# CYUSB_IO.net
KiCad netlist of a schematic drawn in Altium Designer
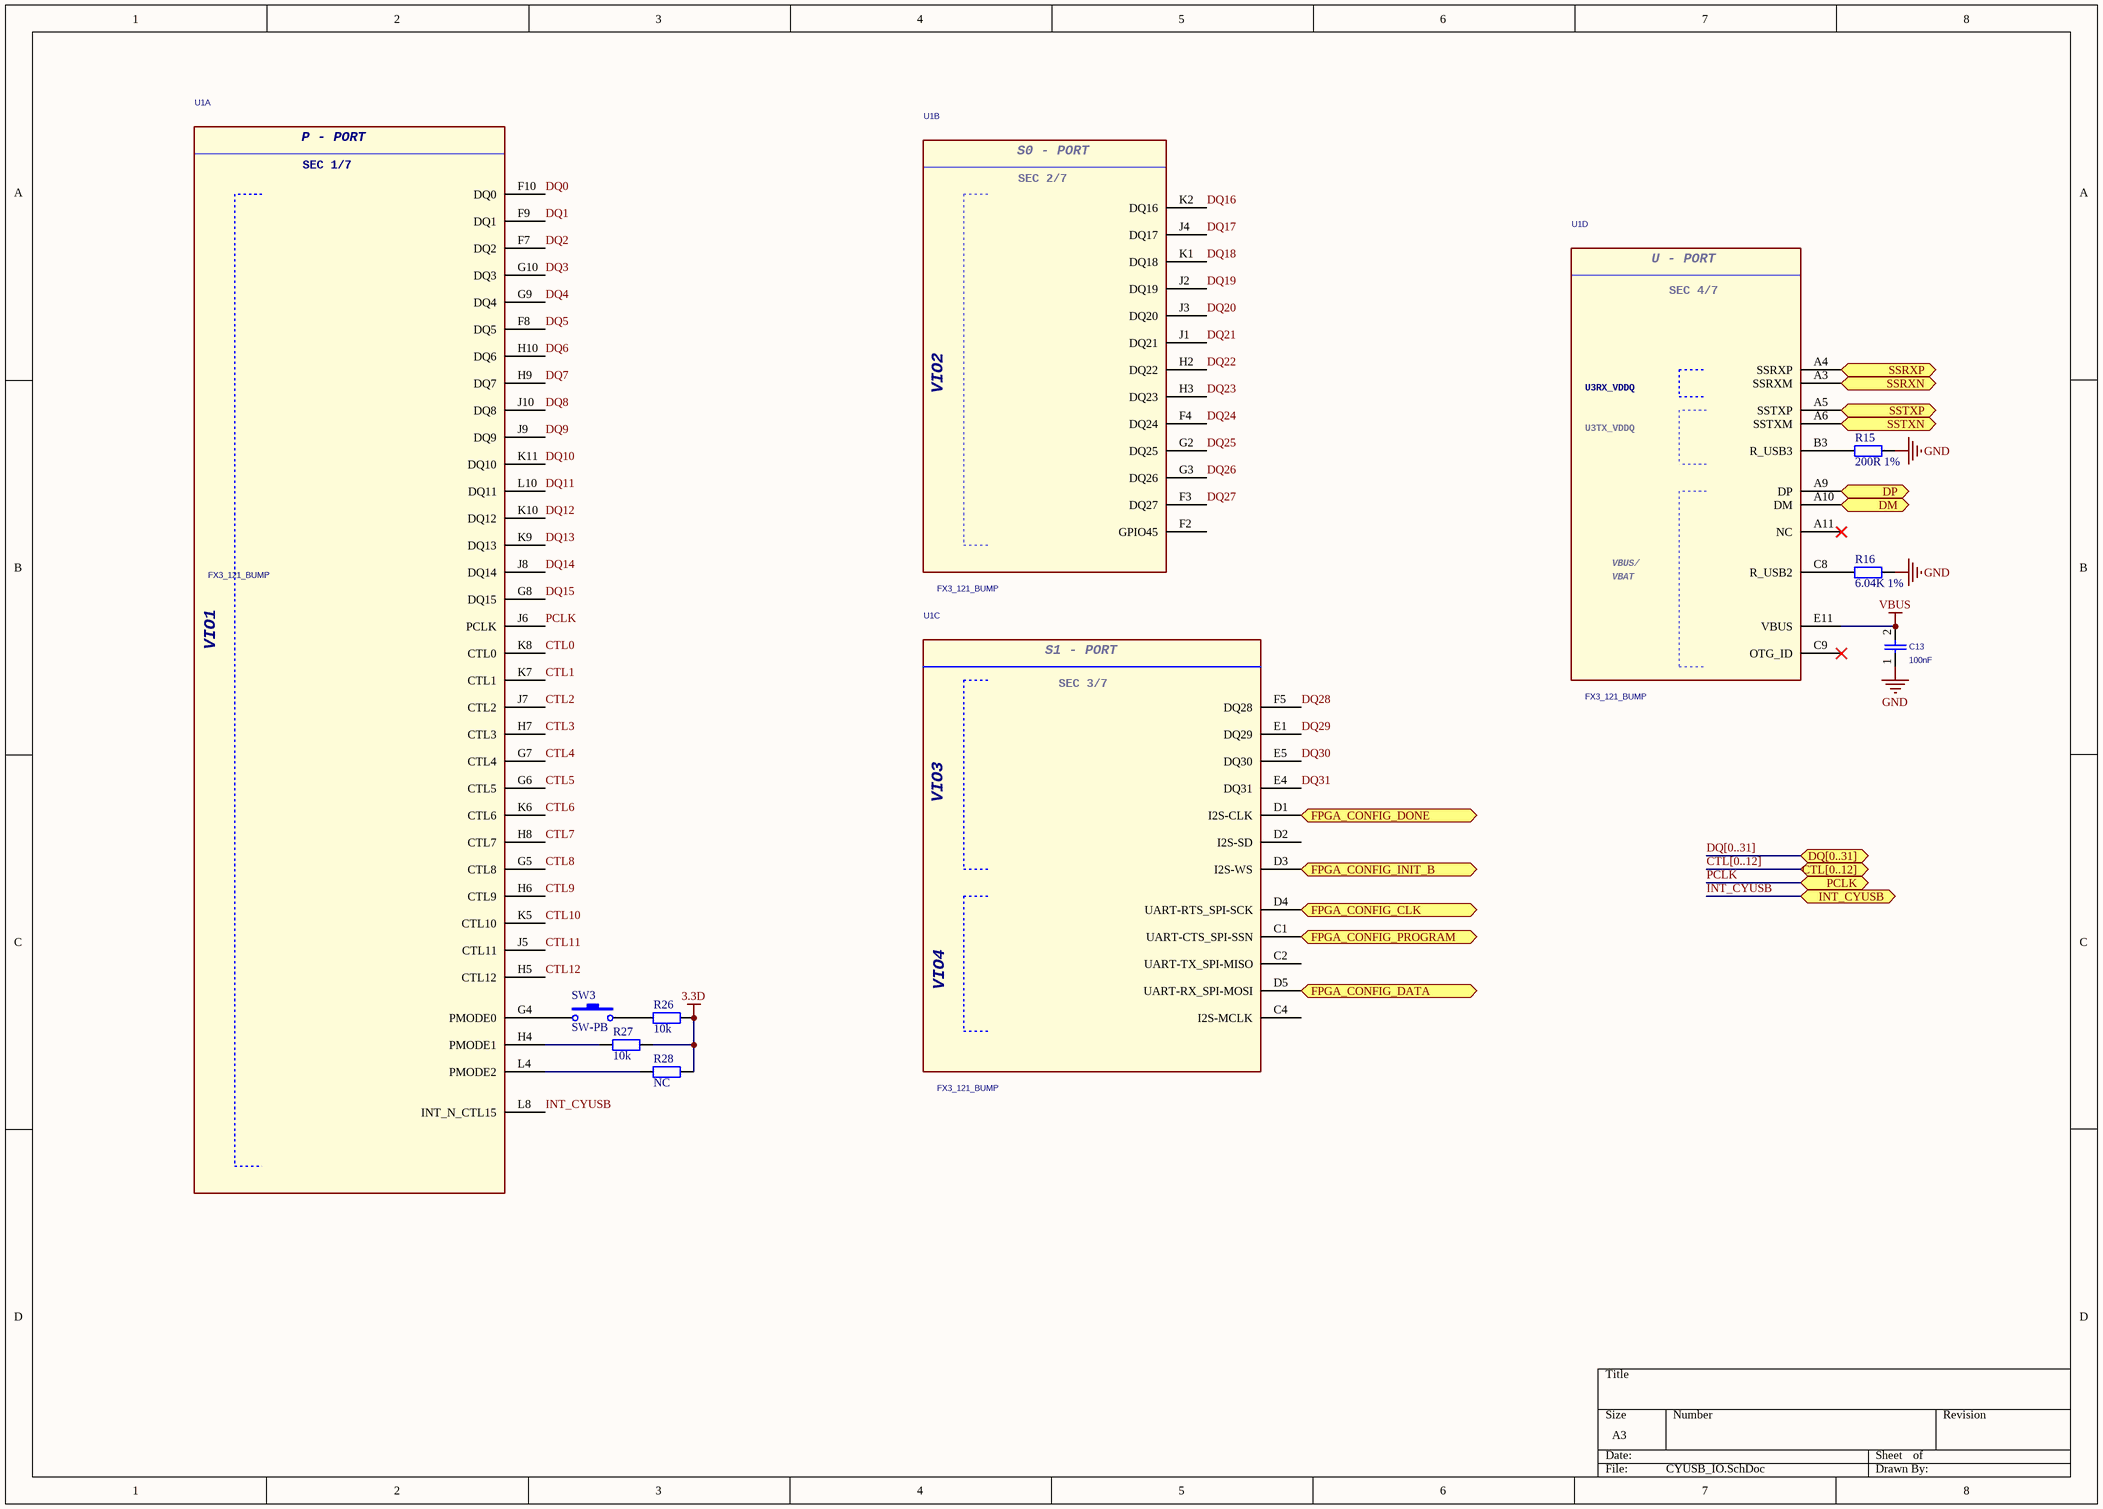
[diagram p0: CYUSB_IO.SchDoc]

(export (version "E")
  (design (tool "Eeschema 10.0.6"))
  (components
    (comp (ref "C13") (value "100nF") (footprint "0201") (libsource (lib "*") (part "CAP/0402")))
    (comp (ref "R15")
      (value "200R 1%")
      (footprint "0201")
      (description "Resistor")
      (fields (field (name "PUBLISHER") "Altium Limited"))
      (libsource (lib "RTC6705") (part "Res2"))
    )
    (comp (ref "R16")
      (value "6.04K 1%")
      (footprint "0201")
      (description "Resistor")
      (fields (field (name "PUBLISHER") "Altium Limited"))
      (libsource (lib "RTC6705") (part "Res2"))
    )
    (comp (ref "R26")
      (value "10k")
      (footprint "0201")
      (description "Resistor")
      (fields (field (name "PUBLISHER") "Altium Limited"))
      (libsource (lib "") (part "Res2_1"))
    )
    (comp (ref "R27")
      (value "10k")
      (footprint "0201")
      (description "Resistor")
      (fields (field (name "PUBLISHER") "Altium Limited"))
      (libsource (lib "") (part "Res2_1"))
    )
    (comp (ref "R28")
      (value "NC")
      (footprint "0201")
      (description "Resistor")
      (fields (field (name "PUBLISHER") "Altium Limited"))
      (libsource (lib "") (part "Res2_1"))
    )
    (comp (ref "SW3")
      (value "SW-PB")
      (footprint "SW-SIDE")
      (description "Switch")
      (fields (field (name "PUBLISHER") "Altium Limited"))
      (libsource (lib "Miscellaneous Devices") (part "SW-PB"))
    )
    (comp (ref "U1")
      (value "FX3_121_BUMP")
      (footprint "FX3_121_BUMP")
      (description "FX3")
      (fields (field (name "MANUFACTURER") "Cypress"))
      (libsource (lib "cyusb3014") (part "FX3_121_BUMP_10"))
    )
  )
  (nets
    (net (code "1") (name "/CTL0") (class "Default")
      (node (ref "U1") (pin "K8") (pinfunction "CTL0_K8") (pintype "passive"))
    )
    (net (code "2") (name "/CTL1") (class "Default")
      (node (ref "U1") (pin "K7") (pinfunction "CTL1_K7") (pintype "passive"))
    )
    (net (code "3") (name "/CTL2") (class "Default")
      (node (ref "U1") (pin "J7") (pinfunction "CTL2_J7") (pintype "passive"))
    )
    (net (code "4") (name "/CTL3") (class "Default")
      (node (ref "U1") (pin "H7") (pinfunction "CTL3_H7") (pintype "passive"))
    )
    (net (code "5") (name "/CTL4") (class "Default")
      (node (ref "U1") (pin "G7") (pinfunction "CTL4_G7") (pintype "passive"))
    )
    (net (code "6") (name "/CTL5") (class "Default")
      (node (ref "U1") (pin "G6") (pinfunction "CTL5_G6") (pintype "passive"))
    )
    (net (code "7") (name "/CTL6") (class "Default")
      (node (ref "U1") (pin "K6") (pinfunction "CTL6_K6") (pintype "passive"))
    )
    (net (code "8") (name "/CTL7") (class "Default")
      (node (ref "U1") (pin "H8") (pinfunction "CTL7_H8") (pintype "passive"))
    )
    (net (code "9") (name "/CTL8") (class "Default")
      (node (ref "U1") (pin "G5") (pinfunction "CTL8_G5") (pintype "passive"))
    )
    (net (code "10") (name "/CTL9") (class "Default")
      (node (ref "U1") (pin "H6") (pinfunction "CTL9_H6") (pintype "passive"))
    )
    (net (code "11") (name "/CTL10") (class "Default")
      (node (ref "U1") (pin "K5") (pinfunction "CTL10_K5") (pintype "passive"))
    )
    (net (code "12") (name "/CTL11") (class "Default")
      (node (ref "U1") (pin "J5") (pinfunction "CTL11_J5") (pintype "passive"))
    )
    (net (code "13") (name "/CTL12") (class "Default")
      (node (ref "U1") (pin "H5") (pinfunction "CTL12_H5") (pintype "passive"))
    )
    (net (code "15") (name "/DM") (class "Default")
      (node (ref "U1") (pin "A10") (pinfunction "DM_A10") (pintype "passive"))
    )
    (net (code "16") (name "/DP") (class "Default")
      (node (ref "U1") (pin "A9") (pinfunction "DP_A9") (pintype "passive"))
    )
    (net (code "17") (name "/DQ0") (class "Default")
      (node (ref "U1") (pin "F10") (pinfunction "DQ0_F10") (pintype "passive"))
    )
    (net (code "18") (name "/DQ1") (class "Default")
      (node (ref "U1") (pin "F9") (pinfunction "DQ1_F9") (pintype "passive"))
    )
    (net (code "19") (name "/DQ2") (class "Default")
      (node (ref "U1") (pin "F7") (pinfunction "DQ2_F7") (pintype "passive"))
    )
    (net (code "20") (name "/DQ3") (class "Default")
      (node (ref "U1") (pin "G10") (pinfunction "DQ3_G10") (pintype "passive"))
    )
    (net (code "21") (name "/DQ4") (class "Default")
      (node (ref "U1") (pin "G9") (pinfunction "DQ4_G9") (pintype "passive"))
    )
    (net (code "22") (name "/DQ5") (class "Default")
      (node (ref "U1") (pin "F8") (pinfunction "DQ5_F8") (pintype "passive"))
    )
    (net (code "23") (name "/DQ6") (class "Default")
      (node (ref "U1") (pin "H10") (pinfunction "DQ6_H10") (pintype "passive"))
    )
    (net (code "24") (name "/DQ7") (class "Default")
      (node (ref "U1") (pin "H9") (pinfunction "DQ7_H9") (pintype "passive"))
    )
    (net (code "25") (name "/DQ8") (class "Default")
      (node (ref "U1") (pin "J10") (pinfunction "DQ8_J10") (pintype "passive"))
    )
    (net (code "26") (name "/DQ9") (class "Default")
      (node (ref "U1") (pin "J9") (pinfunction "DQ9_J9") (pintype "passive"))
    )
    (net (code "27") (name "/DQ10") (class "Default")
      (node (ref "U1") (pin "K11") (pinfunction "DQ10_K11") (pintype "passive"))
    )
    (net (code "28") (name "/DQ11") (class "Default")
      (node (ref "U1") (pin "L10") (pinfunction "DQ11_L10") (pintype "passive"))
    )
    (net (code "29") (name "/DQ12") (class "Default")
      (node (ref "U1") (pin "K10") (pinfunction "DQ12_K10") (pintype "passive"))
    )
    (net (code "30") (name "/DQ13") (class "Default")
      (node (ref "U1") (pin "K9") (pinfunction "DQ13_K9") (pintype "passive"))
    )
    (net (code "31") (name "/DQ14") (class "Default")
      (node (ref "U1") (pin "J8") (pinfunction "DQ14_J8") (pintype "passive"))
    )
    (net (code "32") (name "/DQ15") (class "Default")
      (node (ref "U1") (pin "G8") (pinfunction "DQ15_G8") (pintype "passive"))
    )
    (net (code "33") (name "/DQ16") (class "Default")
      (node (ref "U1") (pin "K2") (pinfunction "DQ16_K2") (pintype "passive"))
    )
    (net (code "34") (name "/DQ17") (class "Default")
      (node (ref "U1") (pin "J4") (pinfunction "DQ17_J4") (pintype "passive"))
    )
    (net (code "35") (name "/DQ18") (class "Default")
      (node (ref "U1") (pin "K1") (pinfunction "DQ18_K1") (pintype "passive"))
    )
    (net (code "36") (name "/DQ19") (class "Default")
      (node (ref "U1") (pin "J2") (pinfunction "DQ19_J2") (pintype "passive"))
    )
    (net (code "37") (name "/DQ20") (class "Default")
      (node (ref "U1") (pin "J3") (pinfunction "DQ20_J3") (pintype "passive"))
    )
    (net (code "38") (name "/DQ21") (class "Default")
      (node (ref "U1") (pin "J1") (pinfunction "DQ21_J1") (pintype "passive"))
    )
    (net (code "39") (name "/DQ22") (class "Default")
      (node (ref "U1") (pin "H2") (pinfunction "DQ22_H2") (pintype "passive"))
    )
    (net (code "40") (name "/DQ23") (class "Default")
      (node (ref "U1") (pin "H3") (pinfunction "DQ23_H3") (pintype "passive"))
    )
    (net (code "41") (name "/DQ24") (class "Default")
      (node (ref "U1") (pin "F4") (pinfunction "DQ24_F4") (pintype "passive"))
    )
    (net (code "42") (name "/DQ25") (class "Default")
      (node (ref "U1") (pin "G2") (pinfunction "DQ25_G2") (pintype "passive"))
    )
    (net (code "43") (name "/DQ26") (class "Default")
      (node (ref "U1") (pin "G3") (pinfunction "DQ26_G3") (pintype "passive"))
    )
    (net (code "44") (name "/DQ27") (class "Default")
      (node (ref "U1") (pin "F3") (pinfunction "DQ27_F3") (pintype "passive"))
    )
    (net (code "45") (name "/DQ28") (class "Default")
      (node (ref "U1") (pin "F5") (pinfunction "DQ28_F5") (pintype "passive"))
    )
    (net (code "46") (name "/DQ29") (class "Default")
      (node (ref "U1") (pin "E1") (pinfunction "DQ29_E1") (pintype "passive"))
    )
    (net (code "47") (name "/DQ30") (class "Default")
      (node (ref "U1") (pin "E5") (pinfunction "DQ30_E5") (pintype "passive"))
    )
    (net (code "48") (name "/DQ31") (class "Default")
      (node (ref "U1") (pin "E4") (pinfunction "DQ31_E4") (pintype "passive"))
    )
    (net (code "50") (name "/FPGA_CONFIG_CLK") (class "Default")
      (node (ref "U1") (pin "D4") (pinfunction "UART-RTS_SPI-SCK_D4") (pintype "passive"))
    )
    (net (code "51") (name "/FPGA_CONFIG_DATA") (class "Default")
      (node (ref "U1") (pin "D5") (pinfunction "UART-RX_SPI-MOSI_D5") (pintype "passive"))
    )
    (net (code "52") (name "/FPGA_CONFIG_DONE") (class "Default")
      (node (ref "U1") (pin "D1") (pinfunction "I2S-CLK_D1") (pintype "passive"))
    )
    (net (code "53") (name "/FPGA_CONFIG_INIT_B") (class "Default")
      (node (ref "U1") (pin "D3") (pinfunction "I2S-WS_D3") (pintype "passive"))
    )
    (net (code "54") (name "/FPGA_CONFIG_PROGRAM") (class "Default")
      (node (ref "U1") (pin "C1") (pinfunction "UART-CTS_SPI-SSN_C1") (pintype "passive"))
    )
    (net (code "55") (name "/INT_CYUSB") (class "Default")
      (node (ref "U1") (pin "L8") (pinfunction "INT_N_CTL15_L8") (pintype "passive"))
    )
    (net (code "56") (name "/PCLK") (class "Default")
      (node (ref "U1") (pin "J6") (pinfunction "PCLK_J6") (pintype "passive"))
    )
    (net (code "57") (name "/SSRXN") (class "Default")
      (node (ref "U1") (pin "A3") (pinfunction "SSRXM_A3") (pintype "passive"))
    )
    (net (code "58") (name "/SSRXP") (class "Default")
      (node (ref "U1") (pin "A4") (pinfunction "SSRXP_A4") (pintype "passive"))
    )
    (net (code "59") (name "/SSTXN") (class "Default")
      (node (ref "U1") (pin "A6") (pinfunction "SSTXM_A6") (pintype "passive"))
    )
    (net (code "60") (name "/SSTXP") (class "Default")
      (node (ref "U1") (pin "A5") (pinfunction "SSTXP_A5") (pintype "passive"))
    )
    (net (code "61") (name "3.3D") (class "Default")
      (node (ref "R26") (pin "1") (pinfunction "1_1") (pintype "passive"))
      (node (ref "R27") (pin "1") (pinfunction "1_1") (pintype "passive"))
      (node (ref "R28") (pin "1") (pinfunction "1_1") (pintype "passive"))
    )
    (net (code "62") (name "GND") (class "Default")
      (node (ref "C13") (pin "1") (pinfunction "1_1") (pintype "passive"))
      (node (ref "R15") (pin "2") (pinfunction "2_2") (pintype "passive"))
      (node (ref "R16") (pin "2") (pinfunction "2_2") (pintype "passive"))
    )
    (net (code "63") (name "Net-(R26-Pad2)") (class "Default")
      (node (ref "R26") (pin "2") (pinfunction "2_2") (pintype "passive"))
      (node (ref "SW3") (pin "2") (pinfunction "2_2") (pintype "passive"))
    )
    (net (code "64") (name "Net-(U1A-PMODE0)") (class "Default")
      (node (ref "SW3") (pin "1") (pinfunction "1_1") (pintype "passive"))
      (node (ref "U1") (pin "G4") (pinfunction "PMODE0_G4") (pintype "passive"))
    )
    (net (code "65") (name "Net-(U1A-PMODE1)") (class "Default")
      (node (ref "R27") (pin "2") (pinfunction "2_2") (pintype "passive"))
      (node (ref "U1") (pin "H4") (pinfunction "PMODE1_H4") (pintype "passive"))
    )
    (net (code "66") (name "Net-(U1A-PMODE2)") (class "Default")
      (node (ref "R28") (pin "2") (pinfunction "2_2") (pintype "passive"))
      (node (ref "U1") (pin "L4") (pinfunction "PMODE2_L4") (pintype "passive"))
    )
    (net (code "67") (name "Net-(U1D-R_USB2)") (class "Default")
      (node (ref "R16") (pin "1") (pinfunction "1_1") (pintype "passive"))
      (node (ref "U1") (pin "C8") (pinfunction "R_USB2_C8") (pintype "passive"))
    )
    (net (code "68") (name "Net-(U1D-R_USB3)") (class "Default")
      (node (ref "R15") (pin "1") (pinfunction "1_1") (pintype "passive"))
      (node (ref "U1") (pin "B3") (pinfunction "R_USB3_B3") (pintype "passive"))
    )
    (net (code "69") (name "VBUS") (class "Default")
      (node (ref "C13") (pin "2") (pinfunction "2_2") (pintype "passive"))
      (node (ref "U1") (pin "E11") (pinfunction "VBUS_E11") (pintype "passive"))
    )
    (net (code "70") (name "unconnected-(U1B-GPIO45-PadF2)") (class "Default")
      (node (ref "U1") (pin "F2") (pinfunction "GPIO45_F2") (pintype "passive"))
    )
    (net (code "71") (name "unconnected-(U1C-I2S-MCLK-PadC4)") (class "Default")
      (node (ref "U1") (pin "C4") (pinfunction "I2S-MCLK_C4") (pintype "passive"))
    )
    (net (code "72") (name "unconnected-(U1C-I2S-SD-PadD2)") (class "Default")
      (node (ref "U1") (pin "D2") (pinfunction "I2S-SD_D2") (pintype "passive"))
    )
    (net (code "73") (name "unconnected-(U1C-UART-TX_SPI-MISO-PadC2)") (class "Default")
      (node (ref "U1") (pin "C2") (pinfunction "UART-TX_SPI-MISO_C2") (pintype "passive"))
    )
    (net (code "74") (name "unconnected-(U1D-NC-PadA11)") (class "Default")
      (node (ref "U1") (pin "A11") (pinfunction "NC_A11") (pintype "passive+no_connect"))
    )
    (net (code "75") (name "unconnected-(U1D-OTG_ID-PadC9)") (class "Default")
      (node (ref "U1") (pin "C9") (pinfunction "OTG_ID_C9") (pintype "passive+no_connect"))
    )
  )
)
